# 09_-_Power.net
KiCad netlist of a schematic drawn in Altium Designer
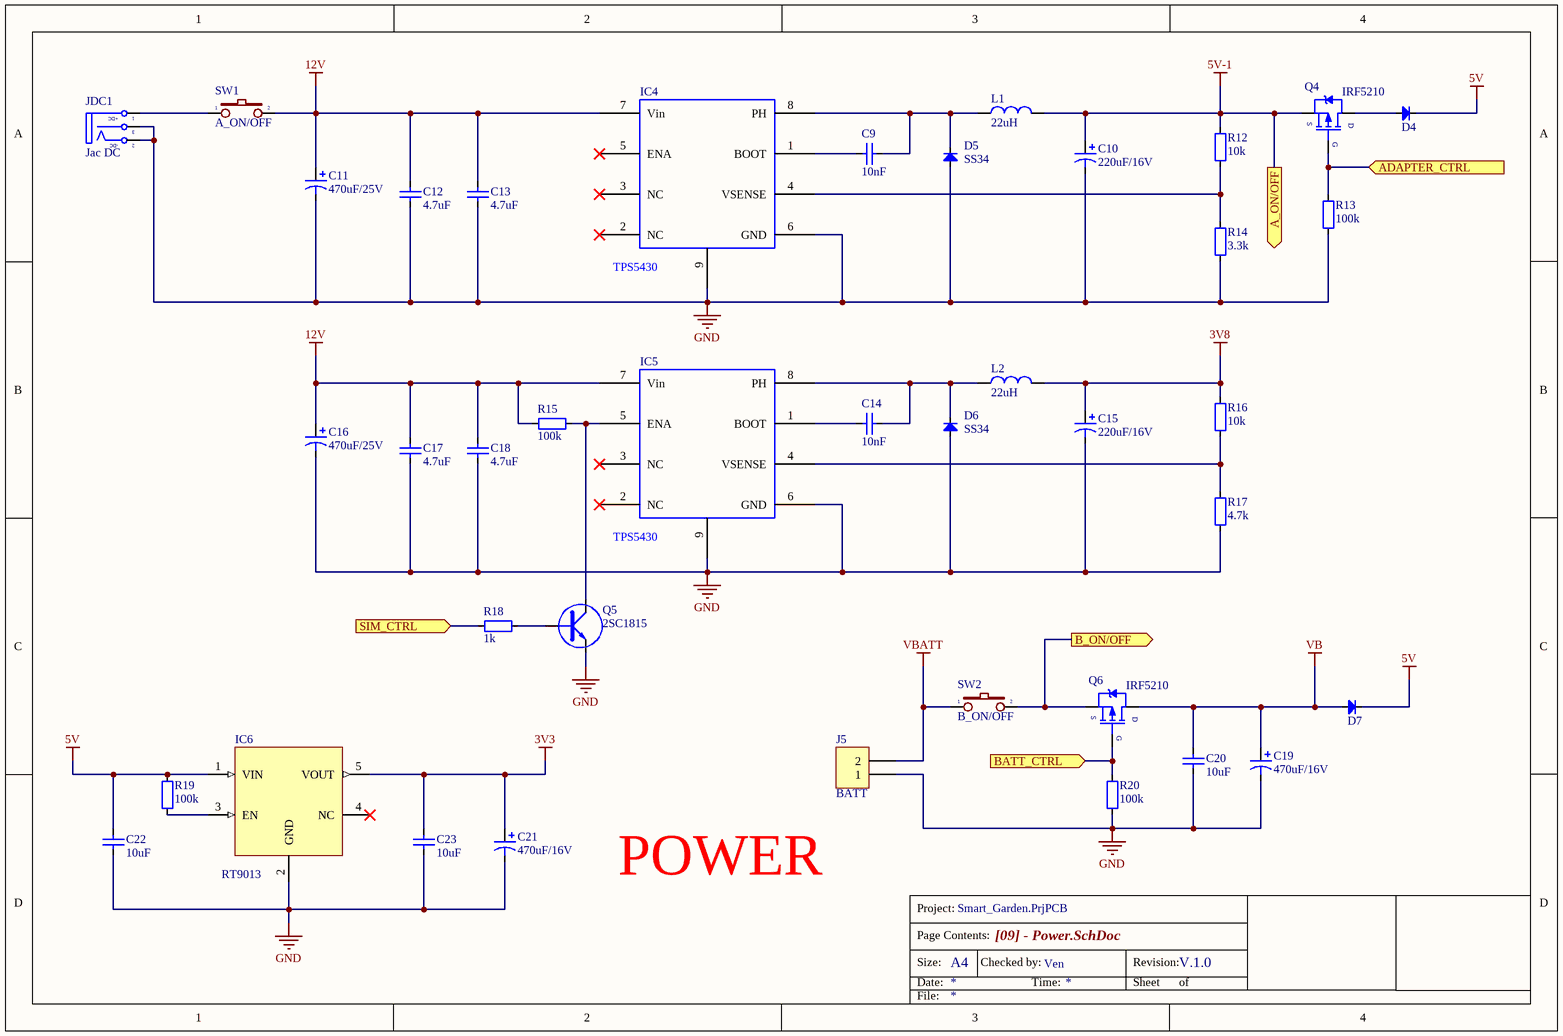
[diagram p0: [09] - Power.SchDoc]

(export (version "E")
  (design (tool "Eeschema 10.0.6"))
  (components
    (comp (ref "C9")
      (value "10nF")
      (footprint "CAP_0805")
      (description "Capacitor")
      (fields (field (name "PUBLISHER") "Altium Limited"))
      (libsource (lib "My Library") (part "CapSMD"))
    )
    (comp (ref "C10")
      (value "220uF/16V")
      (footprint "C8mm")
      (description "Polarized Capacitor (Axial)")
      (fields (field (name "PUBLISHER") "Altium Limited"))
      (libsource (lib "My Library") (part "Cap Pol"))
    )
    (comp (ref "C11")
      (value "470uF/25V")
      (footprint "C8mm")
      (description "Polarized Capacitor (Axial)")
      (fields (field (name "PUBLISHER") "Altium Limited"))
      (libsource (lib "My Library") (part "Cap Pol"))
    )
    (comp (ref "C12")
      (value "4.7uF")
      (footprint "CAP_0805")
      (description "Capacitor")
      (fields (field (name "PUBLISHER") "Altium Limited"))
      (libsource (lib "My Library") (part "CapSMD"))
    )
    (comp (ref "C13")
      (value "4.7uF")
      (footprint "CAP_0805")
      (description "Capacitor")
      (fields (field (name "PUBLISHER") "Altium Limited"))
      (libsource (lib "My Library") (part "CapSMD"))
    )
    (comp (ref "C14")
      (value "10nF")
      (footprint "CAP_0805")
      (description "Capacitor")
      (fields (field (name "PUBLISHER") "Altium Limited"))
      (libsource (lib "My Library") (part "CapSMD"))
    )
    (comp (ref "C15")
      (value "220uF/16V")
      (footprint "C8mm")
      (description "Polarized Capacitor (Axial)")
      (fields (field (name "PUBLISHER") "Altium Limited"))
      (libsource (lib "My Library") (part "Cap Pol"))
    )
    (comp (ref "C16")
      (value "470uF/25V")
      (footprint "C8mm")
      (description "Polarized Capacitor (Axial)")
      (fields (field (name "PUBLISHER") "Altium Limited"))
      (libsource (lib "My Library") (part "Cap Pol"))
    )
    (comp (ref "C17")
      (value "4.7uF")
      (footprint "CAP_0805")
      (description "Capacitor")
      (fields (field (name "PUBLISHER") "Altium Limited"))
      (libsource (lib "My Library") (part "CapSMD"))
    )
    (comp (ref "C18")
      (value "4.7uF")
      (footprint "CAP_0805")
      (description "Capacitor")
      (fields (field (name "PUBLISHER") "Altium Limited"))
      (libsource (lib "My Library") (part "CapSMD"))
    )
    (comp (ref "C19")
      (value "470uF/16V")
      (footprint "C8mm")
      (description "Polarized Capacitor (Axial)")
      (fields (field (name "PUBLISHER") "Altium Limited"))
      (libsource (lib "My Library") (part "Cap Pol"))
    )
    (comp (ref "C20")
      (value "10uF")
      (footprint "CAP_0805")
      (description "Capacitor")
      (fields (field (name "PUBLISHER") "Altium Limited"))
      (libsource (lib "My Library") (part "CapSMD"))
    )
    (comp (ref "C21")
      (value "470uF/16V")
      (footprint "C8mm")
      (description "Polarized Capacitor (Axial)")
      (fields (field (name "PUBLISHER") "Altium Limited"))
      (libsource (lib "My Library") (part "Cap Pol"))
    )
    (comp (ref "C22")
      (value "10uF")
      (footprint "CAP_0805")
      (description "Capacitor")
      (fields (field (name "PUBLISHER") "Altium Limited"))
      (libsource (lib "My Library") (part "CapSMD"))
    )
    (comp (ref "C23")
      (value "10uF")
      (footprint "CAP_0805")
      (description "Capacitor")
      (fields (field (name "PUBLISHER") "Altium Limited"))
      (libsource (lib "My Library") (part "CapSMD"))
    )
    (comp (ref "D4")
      (value "SS34")
      (footprint "DO-214AC(SMA)")
      (description "Diode Schottky 1N5822 3A 40V SMA")
      (fields (field (name "PUBLISHER") "Altium Limited"))
      (libsource (lib "My Library") (part "Diode SMD"))
    )
    (comp (ref "D5")
      (value "SS34")
      (footprint "DO-214AC(SMA)")
      (description "Diode Schottky 1N5822 3A 40V SMA")
      (fields (field (name "PUBLISHER") "Altium Limited"))
      (libsource (lib "My Library") (part "Diode SMD"))
    )
    (comp (ref "D6")
      (value "SS34")
      (footprint "DO-214AC(SMA)")
      (description "Diode Schottky 1N5822 3A 40V SMA")
      (fields (field (name "PUBLISHER") "Altium Limited"))
      (libsource (lib "My Library") (part "Diode SMD"))
    )
    (comp (ref "D7")
      (value "SS34")
      (footprint "DO-214AC(SMA)")
      (description "Diode Schottky 1N5822 3A 40V SMA")
      (fields (field (name "PUBLISHER") "Altium Limited"))
      (libsource (lib "My Library") (part "Diode SMD"))
    )
    (comp (ref "IC4")
      (value "TPS5430")
      (footprint "TPS5430-2")
      (fields (field (name "NAME") "TPS5430"))
      (libsource (lib "My Library") (part "TPS5430"))
    )
    (comp (ref "IC5")
      (value "TPS5430")
      (footprint "TPS5430-2")
      (fields (field (name "NAME") "TPS5430"))
      (libsource (lib "My Library") (part "TPS5430"))
    )
    (comp (ref "IC6")
      (value "RT9013")
      (footprint "SOT23-5")
      (description "RT9013-33GB IC REG LINEAR 3.3V 500mA SOT23-5")
      (libsource (lib "My Library") (part "RT9013"))
    )
    (comp (ref "J5")
      (value "BATT")
      (footprint "KF2-5.08")
      (fields
        (field (name "MANUFACTURER") "Würth Elektronik eiSos GmbH")
        (field (name "PARTNO") "691103110002")
        (field (name "CREATED BY") "Karrer Zheng")
      )
      (libsource (lib "My Library") (part "KF2"))
    )
    (comp (ref "JDC1")
      (value "Jac DC")
      (footprint "DC-IN")
      (description "Jac DC input")
      (libsource (lib "My Library") (part "DCIN"))
    )
    (comp (ref "L1")
      (value "22uH")
      (footprint "L-SMD-M-7.3x4.5")
      (description "Inductor")
      (libsource (lib "My Library") (part "Inductor"))
    )
    (comp (ref "L2")
      (value "22uH")
      (footprint "L-SMD-M-7.3x4.5")
      (description "Inductor")
      (libsource (lib "My Library") (part "Inductor"))
    )
    (comp (ref "Q4")
      (value "IRF5210")
      (footprint "TO-220")
      (description "IR/Vishay P-Channel MOSFET 40A 100V")
      (libsource (lib "My Library") (part "IRF5210"))
    )
    (comp (ref "Q5")
      (value "2SC1815")
      (footprint "SOT23")
      (description "NPN 600mW, ECB")
      (libsource (lib "My Library") (part "2SC1815"))
    )
    (comp (ref "Q6")
      (value "IRF5210")
      (footprint "TO-220")
      (description "IR/Vishay P-Channel MOSFET 40A 100V")
      (libsource (lib "My Library") (part "IRF5210"))
    )
    (comp (ref "R12")
      (value "10k")
      (footprint "RES-SMD-0805")
      (description "Resistor")
      (fields
        (field (name "MANUFACTURER") "Generic Components")
        (field (name "PUBLISHER") "Altium Hobart Technology Centre")
      )
      (libsource (lib "My Library") (part "Resistor - SMD"))
    )
    (comp (ref "R13")
      (value "100k")
      (footprint "RES-SMD-0805")
      (description "Resistor")
      (fields
        (field (name "MANUFACTURER") "Generic Components")
        (field (name "PUBLISHER") "Altium Hobart Technology Centre")
      )
      (libsource (lib "My Library") (part "Resistor - SMD"))
    )
    (comp (ref "R14")
      (value "3.3k")
      (footprint "RES-SMD-0805")
      (description "Resistor")
      (fields
        (field (name "MANUFACTURER") "Generic Components")
        (field (name "PUBLISHER") "Altium Hobart Technology Centre")
      )
      (libsource (lib "My Library") (part "Resistor - SMD"))
    )
    (comp (ref "R15")
      (value "100k")
      (footprint "RES-SMD-0805")
      (description "Resistor")
      (fields
        (field (name "MANUFACTURER") "Generic Components")
        (field (name "PUBLISHER") "Altium Hobart Technology Centre")
      )
      (libsource (lib "My Library") (part "Resistor - SMD"))
    )
    (comp (ref "R16")
      (value "10k")
      (footprint "RES-SMD-0805")
      (description "Resistor")
      (fields
        (field (name "MANUFACTURER") "Generic Components")
        (field (name "PUBLISHER") "Altium Hobart Technology Centre")
      )
      (libsource (lib "My Library") (part "Resistor - SMD"))
    )
    (comp (ref "R17")
      (value "4.7k")
      (footprint "RES-SMD-0805")
      (description "Resistor")
      (fields
        (field (name "MANUFACTURER") "Generic Components")
        (field (name "PUBLISHER") "Altium Hobart Technology Centre")
      )
      (libsource (lib "My Library") (part "Resistor - SMD"))
    )
    (comp (ref "R18")
      (value "1k")
      (footprint "RES-SMD-0805")
      (description "Resistor")
      (fields
        (field (name "MANUFACTURER") "Generic Components")
        (field (name "PUBLISHER") "Altium Hobart Technology Centre")
      )
      (libsource (lib "My Library") (part "Resistor - SMD"))
    )
    (comp (ref "R19")
      (value "100k")
      (footprint "RES-SMD-0805")
      (description "Resistor")
      (fields
        (field (name "MANUFACTURER") "Generic Components")
        (field (name "PUBLISHER") "Altium Hobart Technology Centre")
      )
      (libsource (lib "My Library") (part "Resistor - SMD"))
    )
    (comp (ref "R20")
      (value "100k")
      (footprint "RES-SMD-0805")
      (description "Resistor")
      (fields
        (field (name "MANUFACTURER") "Generic Components")
        (field (name "PUBLISHER") "Altium Hobart Technology Centre")
      )
      (libsource (lib "My Library") (part "Resistor - SMD"))
    )
    (comp (ref "SW1")
      (value "A_ON/OFF")
      (footprint "SW2")
      (description "Switch button 2 pin")
      (libsource (lib "My Library") (part "SW2"))
    )
    (comp (ref "SW2")
      (value "B_ON/OFF")
      (footprint "SW2")
      (description "Switch button 2 pin")
      (libsource (lib "My Library") (part "SW2"))
    )
  )
  (nets
    (net (code "1") (name "/ADAPTER_CTRL") (class "Default")
      (node (ref "Q4") (pin "1") (pinfunction "G_1") (pintype "passive"))
      (node (ref "R13") (pin "2") (pinfunction "2_2") (pintype "passive"))
    )
    (net (code "2") (name "/BATT_CTRL") (class "Default")
      (node (ref "Q6") (pin "1") (pinfunction "G_1") (pintype "passive"))
      (node (ref "R20") (pin "1") (pinfunction "1_1") (pintype "passive"))
    )
    (net (code "3") (name "/B_ON{slash}OFF") (class "Default")
      (node (ref "Q6") (pin "3") (pinfunction "S_3") (pintype "passive"))
      (node (ref "SW2") (pin "2") (pinfunction "2_2") (pintype "passive"))
    )
    (net (code "4") (name "/SIM_CTRL") (class "Default")
      (node (ref "R18") (pin "1") (pinfunction "1_1") (pintype "passive"))
    )
    (net (code "5") (name "3V3") (class "Default")
      (node (ref "C21") (pin "1") (pinfunction "1_1") (pintype "passive"))
      (node (ref "C23") (pin "2") (pinfunction "2_2") (pintype "passive"))
      (node (ref "IC6") (pin "5") (pinfunction "VOUT_5") (pintype "output"))
    )
    (net (code "6") (name "3V8") (class "Default")
      (node (ref "C15") (pin "1") (pinfunction "1_1") (pintype "passive"))
      (node (ref "L2") (pin "2") (pinfunction "2_2") (pintype "passive"))
      (node (ref "R16") (pin "2") (pinfunction "2_2") (pintype "passive"))
    )
    (net (code "7") (name "5V") (class "Default")
      (node (ref "C22") (pin "2") (pinfunction "2_2") (pintype "passive"))
      (node (ref "D4") (pin "2") (pinfunction "K_2") (pintype "passive"))
      (node (ref "D7") (pin "2") (pinfunction "K_2") (pintype "passive"))
      (node (ref "IC6") (pin "1") (pinfunction "VIN_1") (pintype "input"))
      (node (ref "R19") (pin "1") (pinfunction "1_1") (pintype "passive"))
    )
    (net (code "8") (name "5V-1") (class "Default")
      (node (ref "C10") (pin "1") (pinfunction "1_1") (pintype "passive"))
      (node (ref "L1") (pin "2") (pinfunction "2_2") (pintype "passive"))
      (node (ref "Q4") (pin "3") (pinfunction "S_3") (pintype "passive"))
      (node (ref "R12") (pin "2") (pinfunction "2_2") (pintype "passive"))
    )
    (net (code "9") (name "12V") (class "Default")
      (node (ref "C11") (pin "1") (pinfunction "1_1") (pintype "passive"))
      (node (ref "C12") (pin "2") (pinfunction "2_2") (pintype "passive"))
      (node (ref "C13") (pin "2") (pinfunction "2_2") (pintype "passive"))
      (node (ref "C16") (pin "1") (pinfunction "1_1") (pintype "passive"))
      (node (ref "C17") (pin "2") (pinfunction "2_2") (pintype "passive"))
      (node (ref "C18") (pin "2") (pinfunction "2_2") (pintype "passive"))
      (node (ref "IC4") (pin "7") (pinfunction "Vin_7") (pintype "passive"))
      (node (ref "IC5") (pin "7") (pinfunction "Vin_7") (pintype "passive"))
      (node (ref "R15") (pin "1") (pinfunction "1_1") (pintype "passive"))
      (node (ref "SW1") (pin "2") (pinfunction "2_2") (pintype "passive"))
    )
    (net (code "10") (name "GND") (class "Default")
      (node (ref "C10") (pin "2") (pinfunction "2_2") (pintype "passive"))
      (node (ref "C11") (pin "2") (pinfunction "2_2") (pintype "passive"))
      (node (ref "C12") (pin "1") (pinfunction "1_1") (pintype "passive"))
      (node (ref "C13") (pin "1") (pinfunction "1_1") (pintype "passive"))
      (node (ref "C15") (pin "2") (pinfunction "2_2") (pintype "passive"))
      (node (ref "C16") (pin "2") (pinfunction "2_2") (pintype "passive"))
      (node (ref "C17") (pin "1") (pinfunction "1_1") (pintype "passive"))
      (node (ref "C18") (pin "1") (pinfunction "1_1") (pintype "passive"))
      (node (ref "C19") (pin "2") (pinfunction "2_2") (pintype "passive"))
      (node (ref "C20") (pin "1") (pinfunction "1_1") (pintype "passive"))
      (node (ref "C21") (pin "2") (pinfunction "2_2") (pintype "passive"))
      (node (ref "C22") (pin "1") (pinfunction "1_1") (pintype "passive"))
      (node (ref "C23") (pin "1") (pinfunction "1_1") (pintype "passive"))
      (node (ref "D5") (pin "1") (pinfunction "A_1") (pintype "passive"))
      (node (ref "D6") (pin "1") (pinfunction "A_1") (pintype "passive"))
      (node (ref "IC4") (pin "6") (pinfunction "GND_6") (pintype "passive"))
      (node (ref "IC4") (pin "9") (pinfunction "PWR_PAD_9") (pintype "passive"))
      (node (ref "IC5") (pin "6") (pinfunction "GND_6") (pintype "passive"))
      (node (ref "IC5") (pin "9") (pinfunction "PWR_PAD_9") (pintype "passive"))
      (node (ref "IC6") (pin "2") (pinfunction "GND_2") (pintype "passive"))
      (node (ref "J5") (pin "1") (pinfunction "1_1") (pintype "passive"))
      (node (ref "JDC1") (pin "2") (pinfunction "TN_2") (pintype "passive"))
      (node (ref "JDC1") (pin "3") (pinfunction "S_3") (pintype "power_in"))
      (node (ref "Q5") (pin "3") (pinfunction "E_3") (pintype "passive"))
      (node (ref "R13") (pin "1") (pinfunction "1_1") (pintype "passive"))
      (node (ref "R14") (pin "1") (pinfunction "1_1") (pintype "passive"))
      (node (ref "R17") (pin "1") (pinfunction "1_1") (pintype "passive"))
      (node (ref "R20") (pin "2") (pinfunction "2_2") (pintype "passive"))
    )
    (net (code "11") (name "Net-(D4-A)") (class "Default")
      (node (ref "D4") (pin "1") (pinfunction "A_1") (pintype "passive"))
      (node (ref "Q4") (pin "2") (pinfunction "D_2") (pintype "passive"))
    )
    (net (code "12") (name "Net-(D5-K)") (class "Default")
      (node (ref "C9") (pin "1") (pinfunction "1_1") (pintype "passive"))
      (node (ref "D5") (pin "2") (pinfunction "K_2") (pintype "passive"))
      (node (ref "IC4") (pin "8") (pinfunction "PH_8") (pintype "passive"))
      (node (ref "L1") (pin "1") (pinfunction "1_1") (pintype "passive"))
    )
    (net (code "13") (name "Net-(D6-K)") (class "Default")
      (node (ref "C14") (pin "1") (pinfunction "1_1") (pintype "passive"))
      (node (ref "D6") (pin "2") (pinfunction "K_2") (pintype "passive"))
      (node (ref "IC5") (pin "8") (pinfunction "PH_8") (pintype "passive"))
      (node (ref "L2") (pin "1") (pinfunction "1_1") (pintype "passive"))
    )
    (net (code "14") (name "Net-(IC4-BOOT)") (class "Default")
      (node (ref "C9") (pin "2") (pinfunction "2_2") (pintype "passive"))
      (node (ref "IC4") (pin "1") (pinfunction "BOOT_1") (pintype "passive"))
    )
    (net (code "15") (name "Net-(IC4-VSENSE)") (class "Default")
      (node (ref "IC4") (pin "4") (pinfunction "VSENSE_4") (pintype "passive"))
      (node (ref "R12") (pin "1") (pinfunction "1_1") (pintype "passive"))
      (node (ref "R14") (pin "2") (pinfunction "2_2") (pintype "passive"))
    )
    (net (code "16") (name "Net-(IC5-BOOT)") (class "Default")
      (node (ref "C14") (pin "2") (pinfunction "2_2") (pintype "passive"))
      (node (ref "IC5") (pin "1") (pinfunction "BOOT_1") (pintype "passive"))
    )
    (net (code "17") (name "Net-(IC5-ENA)") (class "Default")
      (node (ref "IC5") (pin "5") (pinfunction "ENA_5") (pintype "passive"))
      (node (ref "Q5") (pin "2") (pinfunction "C_2") (pintype "passive"))
      (node (ref "R15") (pin "2") (pinfunction "2_2") (pintype "passive"))
    )
    (net (code "18") (name "Net-(IC5-VSENSE)") (class "Default")
      (node (ref "IC5") (pin "4") (pinfunction "VSENSE_4") (pintype "passive"))
      (node (ref "R16") (pin "1") (pinfunction "1_1") (pintype "passive"))
      (node (ref "R17") (pin "2") (pinfunction "2_2") (pintype "passive"))
    )
    (net (code "19") (name "Net-(IC6-EN)") (class "Default")
      (node (ref "IC6") (pin "3") (pinfunction "EN_3") (pintype "input"))
      (node (ref "R19") (pin "2") (pinfunction "2_2") (pintype "passive"))
    )
    (net (code "20") (name "Net-(JDC1-T)") (class "Default")
      (node (ref "JDC1") (pin "1") (pinfunction "T_1") (pintype "passive"))
      (node (ref "SW1") (pin "1") (pinfunction "1_1") (pintype "passive"))
    )
    (net (code "21") (name "Net-(Q5-B)") (class "Default")
      (node (ref "Q5") (pin "1") (pinfunction "B_1") (pintype "passive"))
      (node (ref "R18") (pin "2") (pinfunction "2_2") (pintype "passive"))
    )
    (net (code "22") (name "VB") (class "Default")
      (node (ref "C19") (pin "1") (pinfunction "1_1") (pintype "passive"))
      (node (ref "C20") (pin "2") (pinfunction "2_2") (pintype "passive"))
      (node (ref "D7") (pin "1") (pinfunction "A_1") (pintype "passive"))
      (node (ref "Q6") (pin "2") (pinfunction "D_2") (pintype "passive"))
    )
    (net (code "23") (name "VBATT") (class "Default")
      (node (ref "J5") (pin "2") (pinfunction "2_2") (pintype "passive"))
      (node (ref "SW2") (pin "1") (pinfunction "1_1") (pintype "passive"))
    )
    (net (code "24") (name "unconnected-(IC4-ENA-Pad5)") (class "Default")
      (node (ref "IC4") (pin "5") (pinfunction "ENA_5") (pintype "passive+no_connect"))
    )
    (net (code "25") (name "unconnected-(IC4-NC-Pad2)") (class "Default")
      (node (ref "IC4") (pin "2") (pinfunction "NC_2") (pintype "passive+no_connect"))
    )
    (net (code "26") (name "unconnected-(IC4-NC-Pad3)") (class "Default")
      (node (ref "IC4") (pin "3") (pinfunction "NC_3") (pintype "passive+no_connect"))
    )
    (net (code "27") (name "unconnected-(IC5-NC-Pad2)") (class "Default")
      (node (ref "IC5") (pin "2") (pinfunction "NC_2") (pintype "passive+no_connect"))
    )
    (net (code "28") (name "unconnected-(IC5-NC-Pad3)") (class "Default")
      (node (ref "IC5") (pin "3") (pinfunction "NC_3") (pintype "passive+no_connect"))
    )
    (net (code "29") (name "unconnected-(IC6-NC-Pad4)") (class "Default")
      (node (ref "IC6") (pin "4") (pinfunction "NC_4") (pintype "passive+no_connect"))
    )
  )
)
